# SCH_Circuit-555_2025-10-19.net
KiCad netlist of a schematic drawn in EasyEDA
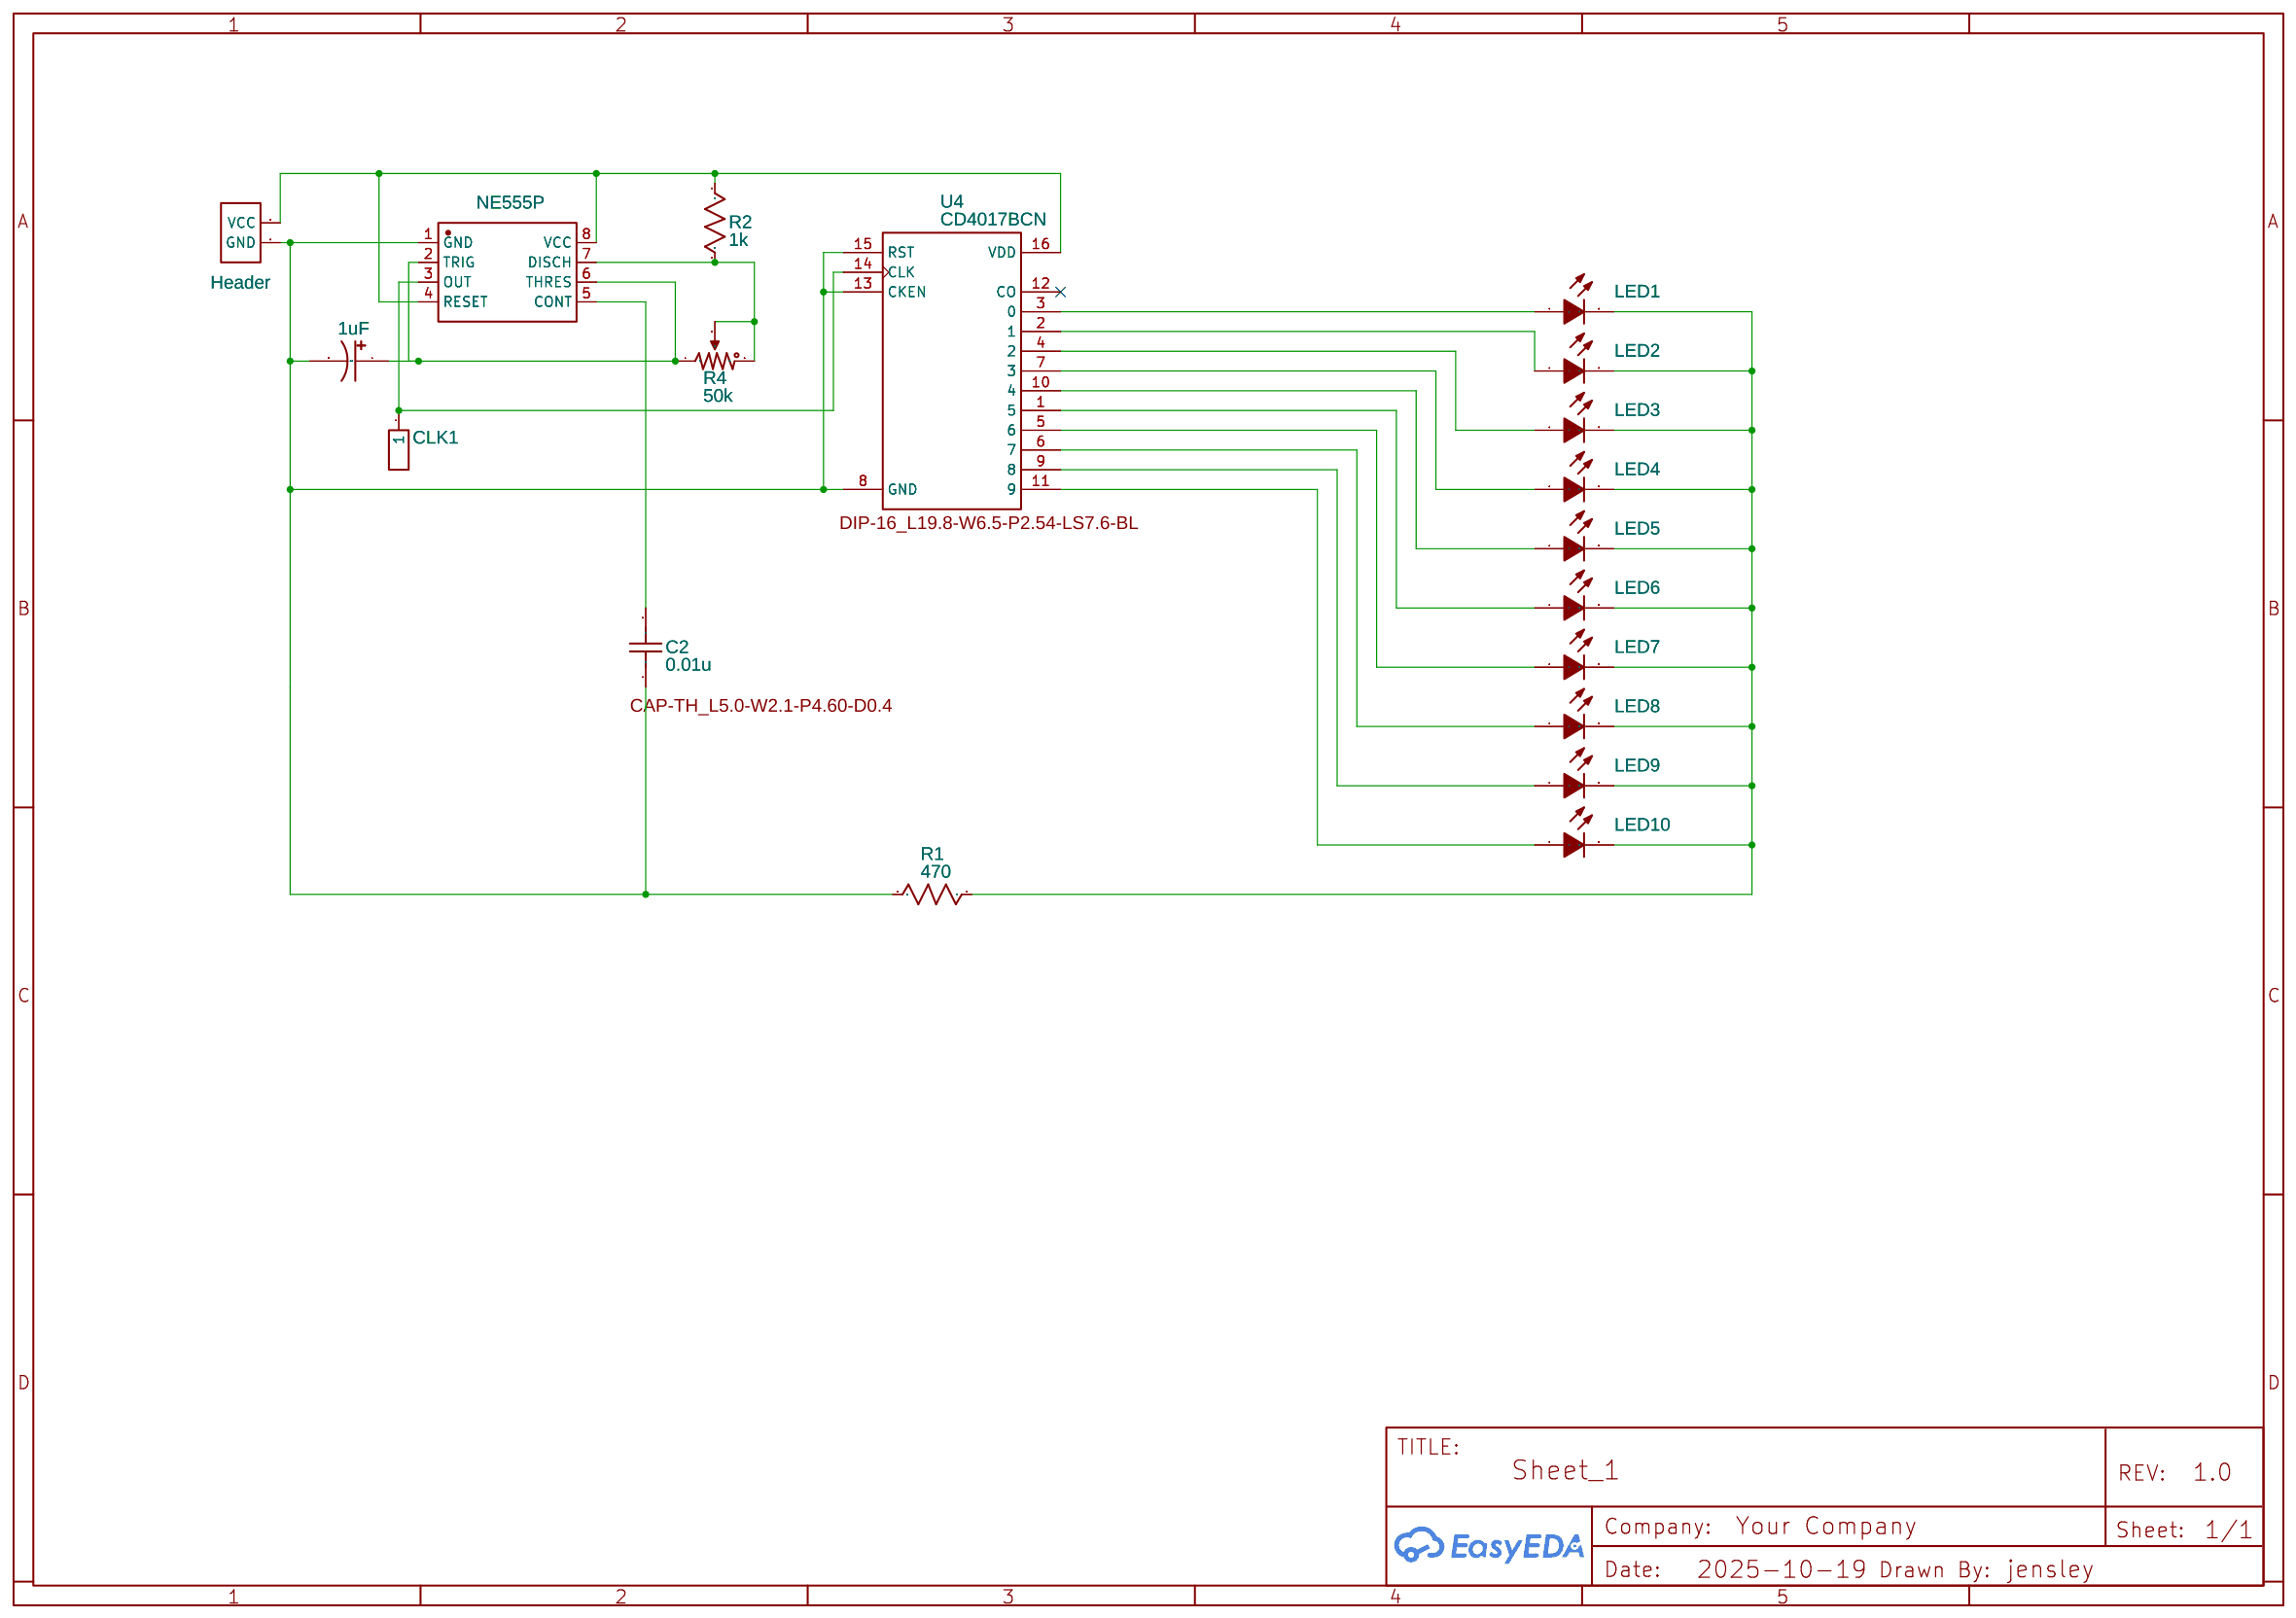
[diagram p0: schematic sheet]

(export (version "E")
  (design (tool "Eeschema 10.0.6"))
  (components
    (comp (ref "C1")
      (value "1uF")
      (fields (field (name "Manufacturer Part") "UVZ1H010MDD") (field (name "Manufacturer") "Nichicon(尼吉康)"))
      (libsource (lib "") (part "UVZ1H010MDD"))
    )
    (comp (ref "C2") (value "0.01u") (libsource (lib "") (part "C_0603_US")))
    (comp (ref "CLK1")
      (value "C81276")
      (fields
        (field (name "Manufacturer Part") "2.54-1*1P针")
        (field (name "Manufacturer") "BOOMELE(Boom Precision Elec)")
      )
      (libsource (lib "") (part "Header-Male-2.54_1x1"))
    )
    (comp (ref "H1") (value "Header") (libsource (lib "") (part "HEADER-FEMALE-2.54_1X2")))
    (comp (ref "LED1") (value "LED_5MM") (libsource (lib "") (part "LED_5MM")))
    (comp (ref "LED2") (value "LED_5MM") (libsource (lib "") (part "LED_5MM")))
    (comp (ref "LED3") (value "LED_5MM") (libsource (lib "") (part "LED_5MM")))
    (comp (ref "LED4") (value "LED_5MM") (libsource (lib "") (part "LED_5MM")))
    (comp (ref "LED5") (value "LED_5MM") (libsource (lib "") (part "LED_5MM")))
    (comp (ref "LED6") (value "LED_5MM") (libsource (lib "") (part "LED_5MM")))
    (comp (ref "LED7") (value "LED_5MM") (libsource (lib "") (part "LED_5MM")))
    (comp (ref "LED8") (value "LED_5MM") (libsource (lib "") (part "LED_5MM")))
    (comp (ref "LED9") (value "LED_5MM") (libsource (lib "") (part "LED_5MM")))
    (comp (ref "LED10") (value "LED_5MM") (libsource (lib "") (part "LED_5MM")))
    (comp (ref "R1")
      (value "470")
      (fields (field (name "Manufacturer Part") "?"))
      (libsource (lib "") (part "Resistor"))
    )
    (comp (ref "R2")
      (value "1k")
      (fields (field (name "Manufacturer Part") "?"))
      (libsource (lib "") (part "Resistor_1"))
    )
    (comp (ref "R4")
      (value "50k")
      (fields (field (name "Manufacturer Part") "?"))
      (libsource (lib "") (part "Potentiometer"))
    )
    (comp (ref "U2")
      (value "NE555P")
      (fields (field (name "Manufacturer") "TI(德州仪器)"))
      (libsource (lib "") (part "NE555P"))
    )
    (comp (ref "U4") (value "CD4017BCN") (libsource (lib "") (part "CD4017BCN")))
  )
  (nets
    (net (code "1") (name "Net-(H1-GND)") (class "Default")
      (node (ref "C1") (pin "2") (pinfunction "2_2") (pintype "unspecified"))
      (node (ref "C2") (pin "1") (pinfunction "1_1") (pintype "unspecified"))
      (node (ref "H1") (pin "2") (pinfunction "GND_2") (pintype "unspecified"))
      (node (ref "R1") (pin "2") (pinfunction "2_2") (pintype "unspecified"))
      (node (ref "U2") (pin "1") (pinfunction "GND_1") (pintype "unspecified"))
      (node (ref "U4") (pin "13") (pinfunction "CKEN_13") (pintype "unspecified"))
      (node (ref "U4") (pin "15") (pinfunction "RST_15") (pintype "unspecified"))
      (node (ref "U4") (pin "8") (pinfunction "GND_8") (pintype "passive"))
    )
    (net (code "2") (name "Net-(H1-VCC)") (class "Default")
      (node (ref "H1") (pin "1") (pinfunction "VCC_1") (pintype "unspecified"))
      (node (ref "R2") (pin "1") (pinfunction "1_1") (pintype "unspecified"))
      (node (ref "U2") (pin "4") (pinfunction "RESET_4") (pintype "unspecified"))
      (node (ref "U2") (pin "8") (pinfunction "VCC_8") (pintype "unspecified"))
      (node (ref "U4") (pin "16") (pinfunction "VDD_16") (pintype "passive"))
    )
    (net (code "3") (name "Net-(LED1-A)") (class "Default")
      (node (ref "LED1") (pin "1") (pinfunction "A_1") (pintype "input"))
      (node (ref "U4") (pin "3") (pinfunction "0_3") (pintype "output"))
    )
    (net (code "4") (name "Net-(LED1-K)") (class "Default")
      (node (ref "LED1") (pin "2") (pinfunction "K_2") (pintype "input"))
      (node (ref "LED10") (pin "2") (pinfunction "K_2") (pintype "input"))
      (node (ref "LED2") (pin "2") (pinfunction "K_2") (pintype "input"))
      (node (ref "LED3") (pin "2") (pinfunction "K_2") (pintype "input"))
      (node (ref "LED4") (pin "2") (pinfunction "K_2") (pintype "input"))
      (node (ref "LED5") (pin "2") (pinfunction "K_2") (pintype "input"))
      (node (ref "LED6") (pin "2") (pinfunction "K_2") (pintype "input"))
      (node (ref "LED7") (pin "2") (pinfunction "K_2") (pintype "input"))
      (node (ref "LED8") (pin "2") (pinfunction "K_2") (pintype "input"))
      (node (ref "LED9") (pin "2") (pinfunction "K_2") (pintype "input"))
      (node (ref "R1") (pin "1") (pinfunction "1_1") (pintype "unspecified"))
    )
    (net (code "5") (name "Net-(LED2-A)") (class "Default")
      (node (ref "LED2") (pin "1") (pinfunction "A_1") (pintype "input"))
      (node (ref "U4") (pin "2") (pinfunction "1_2") (pintype "output"))
    )
    (net (code "6") (name "Net-(LED3-A)") (class "Default")
      (node (ref "LED3") (pin "1") (pinfunction "A_1") (pintype "input"))
      (node (ref "U4") (pin "4") (pinfunction "2_4") (pintype "output"))
    )
    (net (code "7") (name "Net-(LED4-A)") (class "Default")
      (node (ref "LED4") (pin "1") (pinfunction "A_1") (pintype "input"))
      (node (ref "U4") (pin "7") (pinfunction "3_7") (pintype "output"))
    )
    (net (code "8") (name "Net-(LED5-A)") (class "Default")
      (node (ref "LED5") (pin "1") (pinfunction "A_1") (pintype "input"))
      (node (ref "U4") (pin "10") (pinfunction "4_10") (pintype "output"))
    )
    (net (code "9") (name "Net-(LED6-A)") (class "Default")
      (node (ref "LED6") (pin "1") (pinfunction "A_1") (pintype "input"))
      (node (ref "U4") (pin "1") (pinfunction "5_1") (pintype "output"))
    )
    (net (code "10") (name "Net-(LED7-A)") (class "Default")
      (node (ref "LED7") (pin "1") (pinfunction "A_1") (pintype "input"))
      (node (ref "U4") (pin "5") (pinfunction "6_5") (pintype "output"))
    )
    (net (code "11") (name "Net-(LED8-A)") (class "Default")
      (node (ref "LED8") (pin "1") (pinfunction "A_1") (pintype "input"))
      (node (ref "U4") (pin "6") (pinfunction "7_6") (pintype "output"))
    )
    (net (code "12") (name "Net-(LED9-A)") (class "Default")
      (node (ref "LED9") (pin "1") (pinfunction "A_1") (pintype "input"))
      (node (ref "U4") (pin "9") (pinfunction "8_9") (pintype "output"))
    )
    (net (code "13") (name "Net-(LED10-A)") (class "Default")
      (node (ref "LED10") (pin "1") (pinfunction "A_1") (pintype "input"))
      (node (ref "U4") (pin "11") (pinfunction "9_11") (pintype "output"))
    )
    (net (code "14") (name "Net-(R4-2)") (class "Default")
      (node (ref "R2") (pin "2") (pinfunction "2_2") (pintype "unspecified"))
      (node (ref "R4") (pin "2") (pinfunction "3_2") (pintype "unspecified"))
      (node (ref "R4") (pin "3") (pinfunction "2_3") (pintype "unspecified"))
      (node (ref "U2") (pin "7") (pinfunction "DISCH_7") (pintype "unspecified"))
    )
    (net (code "15") (name "Net-(U2-CONT)") (class "Default")
      (node (ref "C2") (pin "2") (pinfunction "2_2") (pintype "unspecified"))
      (node (ref "U2") (pin "5") (pinfunction "CONT_5") (pintype "unspecified"))
    )
    (net (code "16") (name "Net-(U2-OUT)") (class "Default")
      (node (ref "CLK1") (pin "1") (pinfunction "1_1") (pintype "unspecified"))
      (node (ref "U2") (pin "3") (pinfunction "OUT_3") (pintype "unspecified"))
      (node (ref "U4") (pin "14") (pinfunction "CLK_14") (pintype "unspecified"))
    )
    (net (code "17") (name "Net-(U2-THRES)") (class "Default")
      (node (ref "C1") (pin "1") (pinfunction "1_1") (pintype "unspecified"))
      (node (ref "R4") (pin "1") (pinfunction "1_1") (pintype "unspecified"))
      (node (ref "U2") (pin "2") (pinfunction "TRIG_2") (pintype "unspecified"))
      (node (ref "U2") (pin "6") (pinfunction "THRES_6") (pintype "unspecified"))
    )
    (net (code "18") (name "unconnected-(U4-CO-Pad12)") (class "Default")
      (node (ref "U4") (pin "12") (pinfunction "CO_12") (pintype "output+no_connect"))
    )
  )
)
